# Schema_4.net
KiCad netlist of a schematic drawn in EAGLE
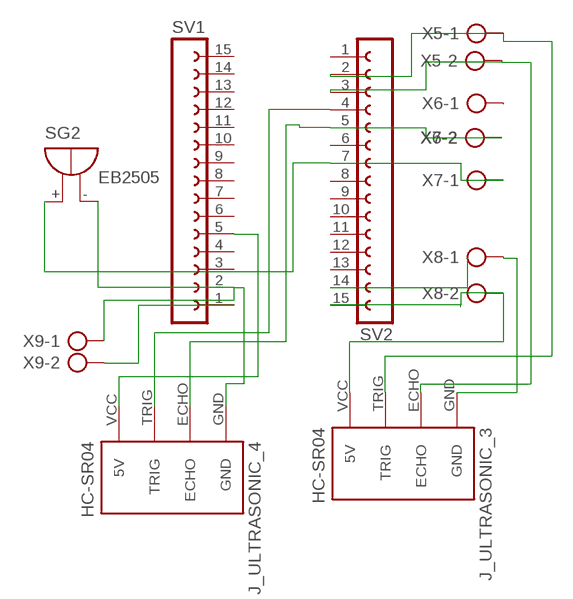
[diagram p0: schematic, sheet 1]

(export (version "E")
  (design (tool "Eeschema 10.0.6"))
  (components
    (comp (ref "J_ULTRASONIC_3")
      (value "HC-SR04")
      (footprint "eagle-import:HC-SR04_FOOTPRINT")
      (libsource (lib "eagle-import") (part "HC-SR04"))
    )
    (comp (ref "J_ULTRASONIC_4")
      (value "HC-SR04")
      (footprint "eagle-import:HC-SR04_FOOTPRINT")
      (libsource (lib "eagle-import") (part "HC-SR04"))
    )
    (comp (ref "SG2")
      (value "EB2505")
      (footprint "eagle-import:EB2505")
      (libsource (lib "eagle-import") (part "EB2505"))
    )
    (comp (ref "SV1")
      (value "FE15-1")
      (footprint "eagle-import:FE15")
      (libsource (lib "eagle-import") (part "FE15-1"))
    )
    (comp (ref "SV2")
      (value "FE15-1")
      (footprint "eagle-import:FE15")
      (libsource (lib "eagle-import") (part "FE15-1"))
    )
    (comp (ref "X5")
      (value "AK300/2")
      (footprint "eagle-import:AK300_2")
      (libsource (lib "eagle-import") (part "AK300/2"))
    )
    (comp (ref "X6")
      (value "AK300/2")
      (footprint "eagle-import:AK300_2")
      (libsource (lib "eagle-import") (part "AK300/2"))
    )
    (comp (ref "X7")
      (value "AK300/2")
      (footprint "eagle-import:AK300_2")
      (libsource (lib "eagle-import") (part "AK300/2"))
    )
    (comp (ref "X8")
      (value "AK300/2")
      (footprint "eagle-import:AK300_2")
      (libsource (lib "eagle-import") (part "AK300/2"))
    )
    (comp (ref "X9")
      (value "AK300/2")
      (footprint "eagle-import:AK300_2")
      (libsource (lib "eagle-import") (part "AK300/2"))
    )
  )
  (nets
    (net (code "1") (name "Net-(J_ULTRASONIC_3-5V)") (class "Default")
      (node (ref "J_ULTRASONIC_3") (pin "VCC") (pinfunction "5V_VCC") (pintype "bidirectional"))
      (node (ref "SV2") (pin "15") (pinfunction "15_15") (pintype "passive"))
      (node (ref "X8") (pin "2") (pinfunction "KL_2") (pintype "passive"))
    )
    (net (code "2") (name "Net-(J_ULTRASONIC_4-5V)") (class "Default")
      (node (ref "J_ULTRASONIC_4") (pin "VCC") (pinfunction "5V_VCC") (pintype "bidirectional"))
      (node (ref "SV1") (pin "5") (pinfunction "5_5") (pintype "passive"))
    )
    (net (code "3") (name "Net-(J_ULTRASONIC_4-PadTRIG)") (class "Default")
      (node (ref "J_ULTRASONIC_4") (pin "TRIG") (pinfunction "TRIG_TRIG") (pintype "bidirectional"))
      (node (ref "SV2") (pin "4") (pinfunction "4_4") (pintype "passive"))
    )
    (net (code "4") (name "Net-(X5A-KL)") (class "Default")
      (node (ref "J_ULTRASONIC_3") (pin "TRIG") (pinfunction "TRIG_TRIG") (pintype "bidirectional"))
      (node (ref "SV2") (pin "2") (pinfunction "2_2") (pintype "passive"))
      (node (ref "X5") (pin "1") (pinfunction "KL_1") (pintype "passive"))
    )
    (net (code "5") (name "Net-(X5B-KL)") (class "Default")
      (node (ref "J_ULTRASONIC_3") (pin "ECHO") (pinfunction "ECHO_ECHO") (pintype "bidirectional"))
      (node (ref "SV2") (pin "3") (pinfunction "3_3") (pintype "passive"))
      (node (ref "X5") (pin "2") (pinfunction "KL_2") (pintype "passive"))
    )
    (net (code "6") (name "Net-(X6B-KL)") (class "Default")
      (node (ref "J_ULTRASONIC_4") (pin "ECHO") (pinfunction "ECHO_ECHO") (pintype "bidirectional"))
      (node (ref "SV2") (pin "5") (pinfunction "5_5") (pintype "passive"))
      (node (ref "X6") (pin "2") (pinfunction "KL_2") (pintype "passive"))
      (node (ref "X7") (pin "2") (pinfunction "KL_2") (pintype "passive"))
    )
    (net (code "7") (name "Net-(X7A-KL)") (class "Default")
      (node (ref "SG2") (pin "+") (pinfunction "+_+") (pintype "passive"))
      (node (ref "SV2") (pin "7") (pinfunction "7_7") (pintype "passive"))
      (node (ref "X7") (pin "1") (pinfunction "KL_1") (pintype "passive"))
    )
    (net (code "8") (name "Net-(X8A-KL)") (class "Default")
      (node (ref "J_ULTRASONIC_3") (pin "GND") (pinfunction "GND_GND") (pintype "bidirectional"))
      (node (ref "X8") (pin "1") (pinfunction "KL_1") (pintype "passive"))
    )
    (net (code "9") (name "Net-(X9A-KL)") (class "Default")
      (node (ref "J_ULTRASONIC_4") (pin "GND") (pinfunction "GND_GND") (pintype "bidirectional"))
      (node (ref "SG2") (pin "-") (pinfunction "-_-") (pintype "passive"))
      (node (ref "SV1") (pin "2") (pinfunction "2_2") (pintype "passive"))
      (node (ref "X9") (pin "1") (pinfunction "KL_1") (pintype "passive"))
    )
    (net (code "10") (name "Net-(X9B-KL)") (class "Default")
      (node (ref "SV1") (pin "1") (pinfunction "1_1") (pintype "passive"))
      (node (ref "X9") (pin "2") (pinfunction "KL_2") (pintype "passive"))
    )
    (net (code "11") (name "unconnected-(SV1-Pad3)") (class "Default")
      (node (ref "SV1") (pin "3") (pinfunction "3_3") (pintype "passive"))
    )
    (net (code "12") (name "unconnected-(SV1-Pad4)") (class "Default")
      (node (ref "SV1") (pin "4") (pinfunction "4_4") (pintype "passive"))
    )
    (net (code "13") (name "unconnected-(SV1-Pad6)") (class "Default")
      (node (ref "SV1") (pin "6") (pinfunction "6_6") (pintype "passive"))
    )
    (net (code "14") (name "unconnected-(SV1-Pad7)") (class "Default")
      (node (ref "SV1") (pin "7") (pinfunction "7_7") (pintype "passive"))
    )
    (net (code "15") (name "unconnected-(SV1-Pad8)") (class "Default")
      (node (ref "SV1") (pin "8") (pinfunction "8_8") (pintype "passive"))
    )
    (net (code "16") (name "unconnected-(SV1-Pad9)") (class "Default")
      (node (ref "SV1") (pin "9") (pinfunction "9_9") (pintype "passive"))
    )
    (net (code "17") (name "unconnected-(SV1-Pad10)") (class "Default")
      (node (ref "SV1") (pin "10") (pinfunction "10_10") (pintype "passive"))
    )
    (net (code "18") (name "unconnected-(SV1-Pad11)") (class "Default")
      (node (ref "SV1") (pin "11") (pinfunction "11_11") (pintype "passive"))
    )
    (net (code "19") (name "unconnected-(SV1-Pad12)") (class "Default")
      (node (ref "SV1") (pin "12") (pinfunction "12_12") (pintype "passive"))
    )
    (net (code "20") (name "unconnected-(SV1-Pad13)") (class "Default")
      (node (ref "SV1") (pin "13") (pinfunction "13_13") (pintype "passive"))
    )
    (net (code "21") (name "unconnected-(SV1-Pad14)") (class "Default")
      (node (ref "SV1") (pin "14") (pinfunction "14_14") (pintype "passive"))
    )
    (net (code "22") (name "unconnected-(SV1-Pad15)") (class "Default")
      (node (ref "SV1") (pin "15") (pinfunction "15_15") (pintype "passive"))
    )
    (net (code "23") (name "unconnected-(SV2-Pad1)") (class "Default")
      (node (ref "SV2") (pin "1") (pinfunction "1_1") (pintype "passive"))
    )
    (net (code "24") (name "unconnected-(SV2-Pad6)") (class "Default")
      (node (ref "SV2") (pin "6") (pinfunction "6_6") (pintype "passive"))
    )
    (net (code "25") (name "unconnected-(SV2-Pad8)") (class "Default")
      (node (ref "SV2") (pin "8") (pinfunction "8_8") (pintype "passive"))
    )
    (net (code "26") (name "unconnected-(SV2-Pad9)") (class "Default")
      (node (ref "SV2") (pin "9") (pinfunction "9_9") (pintype "passive"))
    )
    (net (code "27") (name "unconnected-(SV2-Pad10)") (class "Default")
      (node (ref "SV2") (pin "10") (pinfunction "10_10") (pintype "passive"))
    )
    (net (code "28") (name "unconnected-(SV2-Pad11)") (class "Default")
      (node (ref "SV2") (pin "11") (pinfunction "11_11") (pintype "passive"))
    )
    (net (code "29") (name "unconnected-(SV2-Pad12)") (class "Default")
      (node (ref "SV2") (pin "12") (pinfunction "12_12") (pintype "passive"))
    )
    (net (code "30") (name "unconnected-(SV2-Pad13)") (class "Default")
      (node (ref "SV2") (pin "13") (pinfunction "13_13") (pintype "passive"))
    )
    (net (code "31") (name "unconnected-(SV2-Pad14)") (class "Default")
      (node (ref "SV2") (pin "14") (pinfunction "14_14") (pintype "passive"))
    )
    (net (code "32") (name "unconnected-(X6A-KL-Pad1)") (class "Default")
      (node (ref "X6") (pin "1") (pinfunction "KL_1") (pintype "passive"))
    )
  )
)
